# MODULIQ_ADC_40M_20B_2CH.net
KiCad netlist of a schematic drawn in Altium Designer
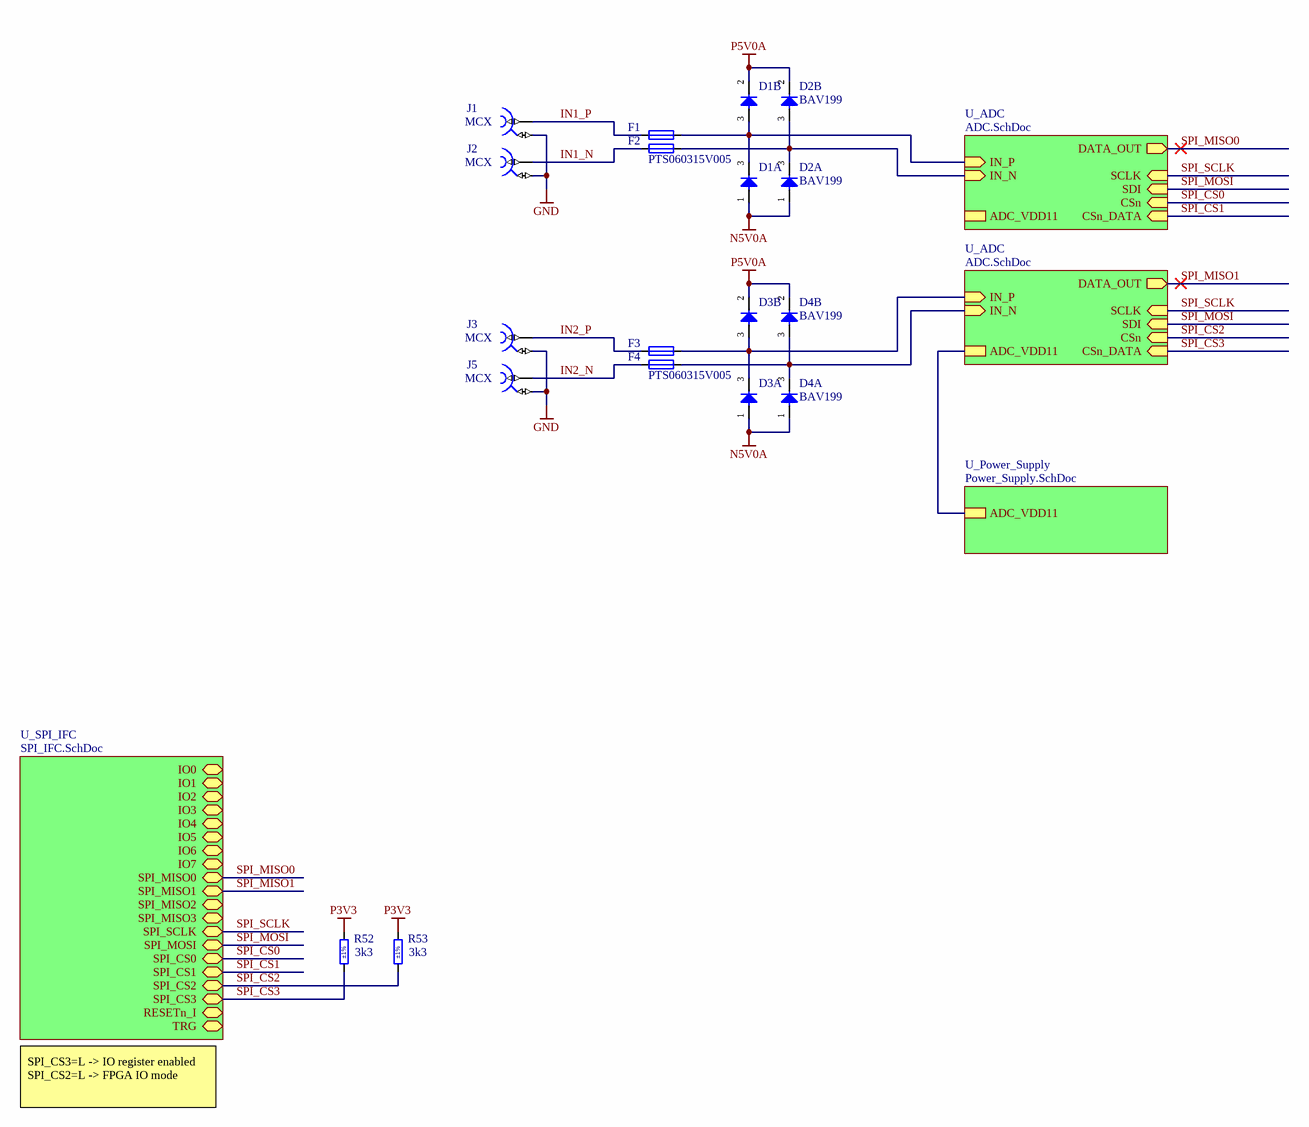
[diagram p0: MODULIQ_ADC_40M_20B_2CH.SchDoc]

(export (version "E")
  (design (tool "Eeschema 10.0.6"))
  (components
    (comp (ref "D1")
      (value "BAV199")
      (footprint "SOT95P240X110-3N")
      (description "Serial Diode")
      (fields
        (field (name "VOLTAGE") "75V")
        (field (name "POWER") "250mW")
        (field (name "AUTHOR") "CERN DEM JMW")
      )
      (libsource (lib "ICs And Semiconductors") (part "Diode x2 A1C3_A3C2"))
    )
    (comp (ref "D2")
      (value "BAV199")
      (footprint "SOT95P240X110-3N")
      (description "Serial Diode")
      (fields
        (field (name "VOLTAGE") "75V")
        (field (name "POWER") "250mW")
        (field (name "AUTHOR") "CERN DEM JMW")
      )
      (libsource (lib "ICs And Semiconductors") (part "Diode x2 A1C3_A3C2"))
    )
    (comp (ref "D3")
      (value "BAV199")
      (footprint "SOT95P240X110-3N")
      (description "Serial Diode")
      (fields
        (field (name "VOLTAGE") "75V")
        (field (name "POWER") "250mW")
        (field (name "AUTHOR") "CERN DEM JMW")
      )
      (libsource (lib "ICs And Semiconductors") (part "Diode x2 A1C3_A3C2"))
    )
    (comp (ref "D4")
      (value "BAV199")
      (footprint "SOT95P240X110-3N")
      (description "Serial Diode")
      (fields
        (field (name "VOLTAGE") "75V")
        (field (name "POWER") "250mW")
        (field (name "AUTHOR") "CERN DEM JMW")
      )
      (libsource (lib "ICs And Semiconductors") (part "Diode x2 A1C3_A3C2"))
    )
    (comp (ref "F1")
      (value "PTS060315V005")
      (footprint "CAPC1709X08N")
      (description "Ptc Reset Fuse 50MA 15V 0603")
      (fields (field (name "MANUFACTURER") "Eaton Bussmann"))
      (libsource (lib "mb") (part "PTS060315V005"))
    )
    (comp (ref "F2")
      (value "PTS060315V005")
      (footprint "CAPC1709X08N")
      (description "Ptc Reset Fuse 50MA 15V 0603")
      (fields (field (name "MANUFACTURER") "Eaton Bussmann"))
      (libsource (lib "mb") (part "PTS060315V005"))
    )
    (comp (ref "F3")
      (value "PTS060315V005")
      (footprint "CAPC1709X08N")
      (description "Ptc Reset Fuse 50MA 15V 0603")
      (fields (field (name "MANUFACTURER") "Eaton Bussmann"))
      (libsource (lib "mb") (part "PTS060315V005"))
    )
    (comp (ref "F4")
      (value "PTS060315V005")
      (footprint "CAPC1709X08N")
      (description "Ptc Reset Fuse 50MA 15V 0603")
      (fields (field (name "MANUFACTURER") "Eaton Bussmann"))
      (libsource (lib "mb") (part "PTS060315V005"))
    )
    (comp (ref "J1")
      (value "MCX")
      (footprint "AMPHENOL_919-109J-51PX")
      (fields
        (field (name "PART NUMBER") "AMPHENOL_919-109J-51PX")
        (field (name "MANUFACTURER") "AMPHENOL")
        (field (name "MANUFACTURER PART NUMBER") "919-109J-51PX (MCX6251B1-3GT30G-50)")
        (field (name "AUTHOR") "CERN DEM BC")
      )
      (libsource (lib "Connectors") (part "Coax_1Female_1Shield"))
    )
    (comp (ref "J2")
      (value "MCX")
      (footprint "AMPHENOL_919-109J-51PX")
      (fields
        (field (name "PART NUMBER") "AMPHENOL_919-109J-51PX")
        (field (name "MANUFACTURER") "AMPHENOL")
        (field (name "MANUFACTURER PART NUMBER") "919-109J-51PX (MCX6251B1-3GT30G-50)")
        (field (name "AUTHOR") "CERN DEM BC")
      )
      (libsource (lib "Connectors") (part "Coax_1Female_1Shield"))
    )
    (comp (ref "J3")
      (value "MCX")
      (footprint "AMPHENOL_919-109J-51PX")
      (fields
        (field (name "PART NUMBER") "AMPHENOL_919-109J-51PX")
        (field (name "MANUFACTURER") "AMPHENOL")
        (field (name "MANUFACTURER PART NUMBER") "919-109J-51PX (MCX6251B1-3GT30G-50)")
        (field (name "AUTHOR") "CERN DEM BC")
      )
      (libsource (lib "Connectors") (part "Coax_1Female_1Shield"))
    )
    (comp (ref "J5")
      (value "MCX")
      (footprint "AMPHENOL_919-109J-51PX")
      (fields
        (field (name "PART NUMBER") "AMPHENOL_919-109J-51PX")
        (field (name "MANUFACTURER") "AMPHENOL")
        (field (name "MANUFACTURER PART NUMBER") "919-109J-51PX (MCX6251B1-3GT30G-50)")
        (field (name "AUTHOR") "CERN DEM BC")
      )
      (libsource (lib "Connectors") (part "Coax_1Female_1Shield"))
    )
    (comp (ref "R52")
      (value "3k3")
      (footprint "RESC1005X40N")
      (description "Resistor - 1%")
      (fields
        (field (name "TOLERANCE") "±1%")
        (field (name "PART NUMBER") "R0402_3K3_1%_0.0625W_100PPM")
        (field (name "POWER") "0.0625W")
        (field (name "AUTHOR") "CERN DEM JLC")
      )
      (libsource (lib "Resistors") (part "Resistor - 1%"))
    )
    (comp (ref "R53")
      (value "3k3")
      (footprint "RESC1005X40N")
      (description "Resistor - 1%")
      (fields
        (field (name "TOLERANCE") "±1%")
        (field (name "PART NUMBER") "R0402_3K3_1%_0.0625W_100PPM")
        (field (name "POWER") "0.0625W")
        (field (name "AUTHOR") "CERN DEM JLC")
      )
      (libsource (lib "Resistors") (part "Resistor - 1%"))
    )
  )
  (nets
    (net (code "5") (name "/IN1_N") (class "Default")
      (node (ref "F2") (pin "1") (pinfunction "1_1") (pintype "passive"))
      (node (ref "J2") (pin "1") (pinfunction "1_1") (pintype "bidirectional"))
    )
    (net (code "6") (name "/IN1_P") (class "Default")
      (node (ref "F1") (pin "1") (pinfunction "1_1") (pintype "passive"))
      (node (ref "J1") (pin "1") (pinfunction "1_1") (pintype "bidirectional"))
    )
    (net (code "7") (name "/IN2_N") (class "Default")
      (node (ref "F4") (pin "1") (pinfunction "1_1") (pintype "passive"))
      (node (ref "J5") (pin "1") (pinfunction "1_1") (pintype "bidirectional"))
    )
    (net (code "8") (name "/IN2_P") (class "Default")
      (node (ref "F3") (pin "1") (pinfunction "1_1") (pintype "passive"))
      (node (ref "J3") (pin "1") (pinfunction "1_1") (pintype "bidirectional"))
    )
    (net (code "9") (name "/IN_N") (class "Default")
      (node (ref "D4") (pin "3") (pinfunction "COMAC_3") (pintype "passive"))
      (node (ref "F4") (pin "2") (pinfunction "2_2") (pintype "passive"))
    )
    (net (code "10") (name "/IN_N_1") (class "Default")
      (node (ref "D2") (pin "3") (pinfunction "COMAC_3") (pintype "passive"))
      (node (ref "F2") (pin "2") (pinfunction "2_2") (pintype "passive"))
    )
    (net (code "11") (name "/IN_P") (class "Default")
      (node (ref "D3") (pin "3") (pinfunction "COMAC_3") (pintype "passive"))
      (node (ref "F3") (pin "2") (pinfunction "2_2") (pintype "passive"))
    )
    (net (code "12") (name "/IN_P_1") (class "Default")
      (node (ref "D1") (pin "3") (pinfunction "COMAC_3") (pintype "passive"))
      (node (ref "F1") (pin "2") (pinfunction "2_2") (pintype "passive"))
    )
    (net (code "24") (name "/SPI_CS2") (class "Default")
      (node (ref "R53") (pin "2") (pinfunction "2_2") (pintype "passive"))
    )
    (net (code "25") (name "/SPI_CS3") (class "Default")
      (node (ref "R52") (pin "2") (pinfunction "2_2") (pintype "passive"))
    )
    (net (code "33") (name "GND") (class "Default")
      (node (ref "J1") (pin "2") (pinfunction "2_2") (pintype "bidirectional"))
      (node (ref "J2") (pin "2") (pinfunction "2_2") (pintype "bidirectional"))
      (node (ref "J3") (pin "2") (pinfunction "2_2") (pintype "bidirectional"))
      (node (ref "J5") (pin "2") (pinfunction "2_2") (pintype "bidirectional"))
    )
    (net (code "34") (name "N5V0A") (class "Default")
      (node (ref "D1") (pin "1") (pinfunction "A_1") (pintype "passive"))
      (node (ref "D2") (pin "1") (pinfunction "A_1") (pintype "passive"))
      (node (ref "D3") (pin "1") (pinfunction "A_1") (pintype "passive"))
      (node (ref "D4") (pin "1") (pinfunction "A_1") (pintype "passive"))
    )
    (net (code "35") (name "P3V3") (class "Default")
      (node (ref "R52") (pin "1") (pinfunction "1_1") (pintype "passive"))
      (node (ref "R53") (pin "1") (pinfunction "1_1") (pintype "passive"))
    )
    (net (code "36") (name "P5V0A") (class "Default")
      (node (ref "D1") (pin "2") (pinfunction "C_2") (pintype "passive"))
      (node (ref "D2") (pin "2") (pinfunction "C_2") (pintype "passive"))
      (node (ref "D3") (pin "2") (pinfunction "C_2") (pintype "passive"))
      (node (ref "D4") (pin "2") (pinfunction "C_2") (pintype "passive"))
    )
  )
)
